# 02_MCU.net
KiCad netlist of a schematic drawn in Altium Designer
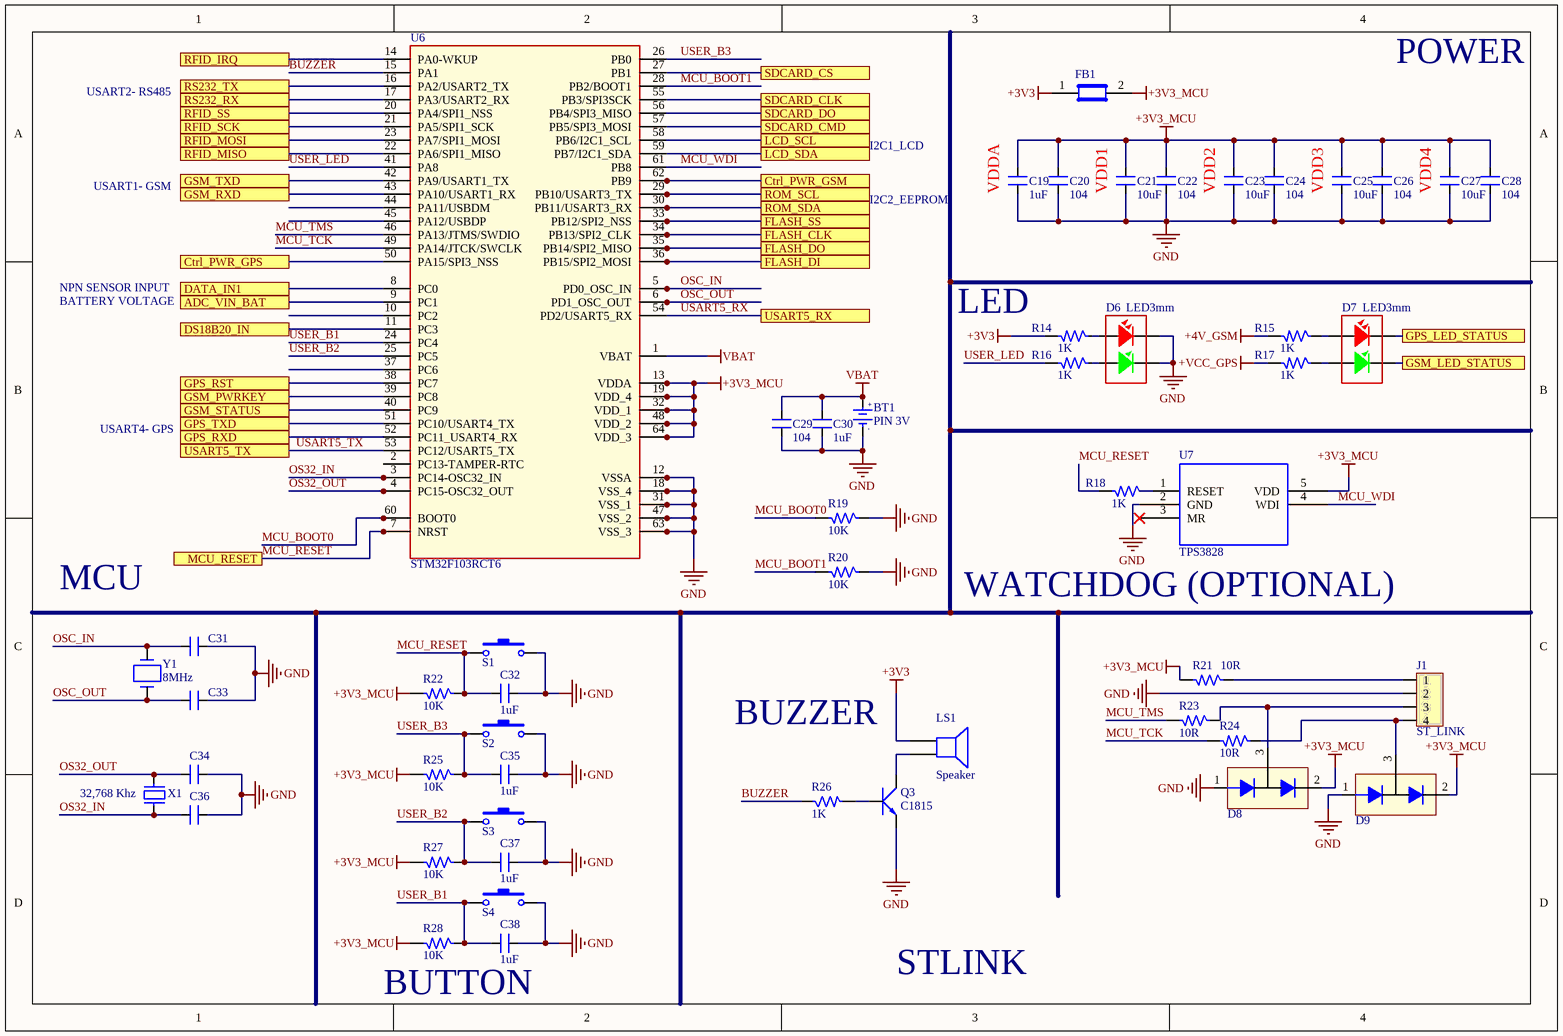
[diagram p0: [02]MCU.SchDoc]

(export (version "E")
  (design (tool "Eeschema 10.0.6"))
  (components
    (comp (ref "BT1")
      (value "PIN 3V")
      (footprint "My Library:CR1220 SMD")
      (description "Battery 3VDC")
      (libsource (lib "My Library") (part "PIN 3V"))
    )
    (comp (ref "C19")
      (value "1uF")
      (footprint "C0603 SMT")
      (description "Cap SMD")
      (libsource (lib "GPS_Traking_V1_1") (part "CM"))
    )
    (comp (ref "C20")
      (value "104")
      (footprint "C0603 SMT")
      (description "Cap SMD")
      (libsource (lib "GPS_Traking_V1_1") (part "CM"))
    )
    (comp (ref "C21")
      (value "10uF")
      (footprint "C0603 SMT")
      (description "Cap SMD")
      (libsource (lib "GPS_Traking_V1_1") (part "CM"))
    )
    (comp (ref "C22")
      (value "104")
      (footprint "C0603 SMT")
      (description "Cap SMD")
      (libsource (lib "GPS_Traking_V1_1") (part "CM"))
    )
    (comp (ref "C23")
      (value "10uF")
      (footprint "C0603 SMT")
      (description "Cap SMD")
      (libsource (lib "GPS_Traking_V1_1") (part "CM"))
    )
    (comp (ref "C24")
      (value "104")
      (footprint "C0603 SMT")
      (description "Cap SMD")
      (libsource (lib "GPS_Traking_V1_1") (part "CM"))
    )
    (comp (ref "C25")
      (value "10uF")
      (footprint "C0603 SMT")
      (description "Cap SMD")
      (libsource (lib "GPS_Traking_V1_1") (part "CM"))
    )
    (comp (ref "C26")
      (value "104")
      (footprint "C0603 SMT")
      (description "Cap SMD")
      (libsource (lib "GPS_Traking_V1_1") (part "CM"))
    )
    (comp (ref "C27")
      (value "10uF")
      (footprint "C0603 SMT")
      (description "Cap SMD")
      (libsource (lib "GPS_Traking_V1_1") (part "CM"))
    )
    (comp (ref "C28")
      (value "104")
      (footprint "C0603 SMT")
      (description "Cap SMD")
      (libsource (lib "GPS_Traking_V1_1") (part "CM"))
    )
    (comp (ref "C29")
      (value "104")
      (footprint "C0603 SMT")
      (description "Cap SMD")
      (libsource (lib "GPS_Traking_V1_1") (part "CM"))
    )
    (comp (ref "C30")
      (value "1uF")
      (footprint "C0603 SMT")
      (description "Cap SMD")
      (libsource (lib "GPS_Traking_V1_1") (part "CM"))
    )
    (comp (ref "C31")
      (value "22pF")
      (footprint "C0603 SMT")
      (description "Cap SMD")
      (libsource (lib "GPS_Traking_V1_1") (part "CM"))
    )
    (comp (ref "C32")
      (value "1uF")
      (footprint "C0603 SMT")
      (description "Cap SMD")
      (libsource (lib "GPS_Traking_V1_1") (part "CM"))
    )
    (comp (ref "C33")
      (value "22pF")
      (footprint "C0603 SMT")
      (description "Cap SMD")
      (libsource (lib "GPS_Traking_V1_1") (part "CM"))
    )
    (comp (ref "C34")
      (value "10pF")
      (footprint "C0603 SMT")
      (description "Cap SMD")
      (libsource (lib "GPS_Traking_V1_1") (part "CM"))
    )
    (comp (ref "C35")
      (value "1uF")
      (footprint "C0603 SMT")
      (description "Cap SMD")
      (libsource (lib "GPS_Traking_V1_1") (part "CM"))
    )
    (comp (ref "C36")
      (value "10pF")
      (footprint "C0603 SMT")
      (description "Cap SMD")
      (libsource (lib "GPS_Traking_V1_1") (part "CM"))
    )
    (comp (ref "C37")
      (value "1uF")
      (footprint "C0603 SMT")
      (description "Cap SMD")
      (libsource (lib "GPS_Traking_V1_1") (part "CM"))
    )
    (comp (ref "C38")
      (value "1uF")
      (footprint "C0603 SMT")
      (description "Cap SMD")
      (libsource (lib "GPS_Traking_V1_1") (part "CM"))
    )
    (comp (ref "D6")
      (value "LED3mm")
      (footprint "GPS_Traking_V1_1:LED 2 holder 3mm")
      (description "LED 2 holder RGB 3mm")
      (libsource (lib "GPS_Traking_V1_1") (part "LED2Holder_3mm"))
    )
    (comp (ref "D7")
      (value "LED3mm")
      (footprint "GPS_Traking_V1_1:LED 2 holder 3mm")
      (description "LED 2 holder RGB 3mm")
      (libsource (lib "GPS_Traking_V1_1") (part "LED2Holder_3mm"))
    )
    (comp (ref "D8")
      (value "DIODE-BAV99")
      (footprint "SOT23")
      (description "ZENER, SOT23,")
      (fields
        (field (name "MANUFACTURER") "ON Semiconductor / Fairchild")
        (field (name "MANUFACTURER PART NUMBER") "BAV99")
        (field (name ".CREATOR") "LeKhaLinh")
        (field (name ".CHECKPCB") "LeKhaLinh")
        (field (name ".CHECKSCH") "LeKhaLinh")
      )
      (libsource (lib "GPS_Traking_V1_1") (part "DIODE-BAV99"))
    )
    (comp (ref "D9")
      (value "DIODE-BAV99")
      (footprint "SOT23")
      (description "ZENER, SOT23,")
      (fields
        (field (name "MANUFACTURER") "ON Semiconductor / Fairchild")
        (field (name "MANUFACTURER PART NUMBER") "BAV99")
        (field (name ".CREATOR") "LeKhaLinh")
        (field (name ".CHECKPCB") "LeKhaLinh")
        (field (name ".CHECKSCH") "LeKhaLinh")
      )
      (libsource (lib "GPS_Traking_V1_1") (part "DIODE-BAV99"))
    )
    (comp (ref "FB1")
      (value "BLM21PG600SN1D")
      (footprint "RES-SMD-0805")
      (description "Ferrite Bead")
      (libsource (lib "khapham") (part "Ferrite Bead"))
    )
    (comp (ref "J1")
      (value "ST_LINK")
      (footprint "CON_4P")
      (description "Header IDC, 4 x 1 Pin Vertical 2.54mm Pitch (Non-Boxed, Male)")
      (fields
        (field (name "MANUFACTURER") "Würth Elektronik eiSos GmbH")
        (field (name "PARTNO") "613002143121")
        (field (name "CREATED BY") "Karrer Zheng")
      )
      (libsource (lib "My Library") (part "Header4"))
    )
    (comp (ref "LS1")
      (value "Speaker")
      (footprint "SPEAKER")
      (description "Loudspeaker")
      (fields (field (name "PUBLISHER") "Altium Limited"))
      (libsource (lib "My Library") (part "Speaker"))
    )
    (comp (ref "Q3")
      (value "C1815")
      (footprint "SOT23B")
      (description "NPN 600mW, ECB")
      (libsource (lib "GPS_Traking_V1_1") (part "C1815"))
    )
    (comp (ref "R14")
      (value "1K")
      (footprint "RES-SMD-0805")
      (description "Resistor SMD")
      (libsource (lib "GPS_Traking_V1_1") (part "RM"))
    )
    (comp (ref "R15")
      (value "1K")
      (footprint "RES-SMD-0805")
      (description "Resistor SMD")
      (libsource (lib "GPS_Traking_V1_1") (part "RM"))
    )
    (comp (ref "R16")
      (value "1K")
      (footprint "RES-SMD-0805")
      (description "Resistor SMD")
      (libsource (lib "GPS_Traking_V1_1") (part "RM"))
    )
    (comp (ref "R17")
      (value "1K")
      (footprint "RES-SMD-0805")
      (description "Resistor SMD")
      (libsource (lib "GPS_Traking_V1_1") (part "RM"))
    )
    (comp (ref "R18")
      (value "1K")
      (footprint "RES-SMD-0603")
      (description "Resistor SMD")
      (libsource (lib "GPS_Traking_V1_1") (part "RM"))
    )
    (comp (ref "R19")
      (value "10K")
      (footprint "R0603 -SMT")
      (description "Resistor SMD")
      (libsource (lib "GPS_Traking_V1_1") (part "RM"))
    )
    (comp (ref "R20")
      (value "10K")
      (footprint "R0603 -SMT")
      (description "Resistor SMD")
      (libsource (lib "GPS_Traking_V1_1") (part "RM"))
    )
    (comp (ref "R21")
      (value "10R")
      (footprint "RES-SMD-0603")
      (description "Resistor SMD")
      (libsource (lib "GPS_Traking_V1_1") (part "RM"))
    )
    (comp (ref "R22")
      (value "10K")
      (footprint "R0603 -SMT")
      (description "Resistor SMD")
      (libsource (lib "GPS_Traking_V1_1") (part "RM"))
    )
    (comp (ref "R23")
      (value "10R")
      (footprint "RES-SMD-0603")
      (description "Resistor SMD")
      (libsource (lib "GPS_Traking_V1_1") (part "RM"))
    )
    (comp (ref "R24")
      (value "10R")
      (footprint "RES-SMD-0603")
      (description "Resistor SMD")
      (libsource (lib "GPS_Traking_V1_1") (part "RM"))
    )
    (comp (ref "R25")
      (value "10K")
      (footprint "R0603 -SMT")
      (description "Resistor SMD")
      (libsource (lib "GPS_Traking_V1_1") (part "RM"))
    )
    (comp (ref "R26")
      (value "1K")
      (footprint "R0603 -SMT")
      (description "Resistor SMD")
      (libsource (lib "GPS_Traking_V1_1") (part "RM"))
    )
    (comp (ref "R27")
      (value "10K")
      (footprint "R0603 -SMT")
      (description "Resistor SMD")
      (libsource (lib "GPS_Traking_V1_1") (part "RM"))
    )
    (comp (ref "R28")
      (value "10K")
      (footprint "R0603 -SMT")
      (description "Resistor SMD")
      (libsource (lib "GPS_Traking_V1_1") (part "RM"))
    )
    (comp (ref "S1")
      (value "SW-SMD")
      (footprint "SW-SMD")
      (description "Switch")
      (fields (field (name "PUBLISHER") "Altium Limited"))
      (libsource (lib "My Library") (part "SW-SMD"))
    )
    (comp (ref "S2")
      (value "SW-SMD")
      (footprint "BUTTON NGHIENG")
      (description "Switch")
      (fields (field (name "PUBLISHER") "Altium Limited"))
      (libsource (lib "My Library") (part "SW-SMD"))
    )
    (comp (ref "S3")
      (value "SW-SMD")
      (footprint "BUTTON NGHIENG")
      (description "Switch")
      (fields (field (name "PUBLISHER") "Altium Limited"))
      (libsource (lib "My Library") (part "SW-SMD"))
    )
    (comp (ref "S4")
      (value "SW-SMD")
      (footprint "BUTTON NGHIENG")
      (description "Switch")
      (fields (field (name "PUBLISHER") "Altium Limited"))
      (libsource (lib "My Library") (part "SW-SMD"))
    )
    (comp (ref "U6")
      (value "STM32F103RCT6")
      (footprint "LQFP-64")
      (description "MCU 32BIT 256KB FLASH 64LQFP")
      (libsource (lib "GPS_Traking_V1_1") (part "STM32F103RCT6"))
    )
    (comp (ref "U7")
      (value "TPS3828")
      (footprint "TPS3828")
      (libsource (lib "GPS_Traking_V1_1") (part "TPS3828"))
    )
    (comp (ref "X1")
      (value "32,768 Khz")
      (footprint "XT32kn")
      (description "Crystal 32,768kHz for timer real")
      (libsource (lib "GPS_Traking_V1_1") (part "XT32k"))
    )
    (comp (ref "Y1")
      (value "8MHz")
      (footprint "GPS_Traking_V1_1:ABM7_v1_1_BIG")
      (description "CRYSTAL 16MHZ 18PF SMD")
      (fields
        (field (name "MANUFACTURER") "Abracon LLC")
        (field (name "MANUFACTURER PART NUMBER") "ABM7-16.000MHZ-D2Y-T")
        (field (name ".CREATOR") "MM")
        (field (name ".CHECKED PCB") "RF")
        (field (name ".CHECKED SCH") "RF")
      )
      (libsource (lib "GPS_Traking_V1_1") (part "ABM7-16.000MHZ-D2Y-T"))
    )
  )
  (nets
    (net (code "1") (name "+3V3") (class "Default")
      (node (ref "FB1") (pin "1") (pinfunction "1_1") (pintype "passive"))
      (node (ref "LS1") (pin "1") (pinfunction "1_1") (pintype "passive"))
      (node (ref "R14") (pin "2") (pinfunction "2_2") (pintype "passive"))
    )
    (net (code "2") (name "+3V3_MCU") (class "Default")
      (node (ref "C19") (pin "2") (pinfunction "2_2") (pintype "passive"))
      (node (ref "C20") (pin "2") (pinfunction "2_2") (pintype "passive"))
      (node (ref "C21") (pin "2") (pinfunction "2_2") (pintype "passive"))
      (node (ref "C22") (pin "2") (pinfunction "2_2") (pintype "passive"))
      (node (ref "C23") (pin "2") (pinfunction "2_2") (pintype "passive"))
      (node (ref "C24") (pin "2") (pinfunction "2_2") (pintype "passive"))
      (node (ref "C25") (pin "2") (pinfunction "2_2") (pintype "passive"))
      (node (ref "C26") (pin "2") (pinfunction "2_2") (pintype "passive"))
      (node (ref "C27") (pin "2") (pinfunction "2_2") (pintype "passive"))
      (node (ref "C28") (pin "2") (pinfunction "2_2") (pintype "passive"))
      (node (ref "D8") (pin "2") (pinfunction "2_2") (pintype "passive"))
      (node (ref "D9") (pin "2") (pinfunction "2_2") (pintype "passive"))
      (node (ref "FB1") (pin "2") (pinfunction "2_2") (pintype "passive"))
      (node (ref "R21") (pin "2") (pinfunction "2_2") (pintype "passive"))
      (node (ref "R22") (pin "2") (pinfunction "2_2") (pintype "passive"))
      (node (ref "R25") (pin "2") (pinfunction "2_2") (pintype "passive"))
      (node (ref "R27") (pin "2") (pinfunction "2_2") (pintype "passive"))
      (node (ref "R28") (pin "2") (pinfunction "2_2") (pintype "passive"))
      (node (ref "U6") (pin "13") (pinfunction "VDDA_13") (pintype "passive"))
      (node (ref "U6") (pin "19") (pinfunction "VDD_4_19") (pintype "passive"))
      (node (ref "U6") (pin "32") (pinfunction "VDD_1_32") (pintype "passive"))
      (node (ref "U6") (pin "48") (pinfunction "VDD_2_48") (pintype "passive"))
      (node (ref "U6") (pin "64") (pinfunction "VDD_3_64") (pintype "passive"))
      (node (ref "U7") (pin "5") (pinfunction "VDD_5") (pintype "power_in"))
    )
    (net (code "3") (name "+4V_GSM") (class "Default")
      (node (ref "R15") (pin "2") (pinfunction "2_2") (pintype "passive"))
    )
    (net (code "4") (name "+VCC_GPS") (class "Default")
      (node (ref "R17") (pin "2") (pinfunction "2_2") (pintype "passive"))
    )
    (net (code "5") (name "/ADC_VIN_BAT") (class "Default")
      (node (ref "U6") (pin "9") (pinfunction "PC1_9") (pintype "passive"))
    )
    (net (code "6") (name "/BUZZER") (class "Default")
      (node (ref "R26") (pin "1") (pinfunction "1_1") (pintype "passive"))
      (node (ref "U6") (pin "15") (pinfunction "PA1_15") (pintype "passive"))
    )
    (net (code "7") (name "/Ctrl_PWR_GPS") (class "Default")
      (node (ref "U6") (pin "50") (pinfunction "PA15/SPI3_NSS_50") (pintype "passive"))
    )
    (net (code "8") (name "/Ctrl_PWR_GSM") (class "Default")
      (node (ref "U6") (pin "62") (pinfunction "PB9_62") (pintype "passive"))
    )
    (net (code "9") (name "/DATA_IN1") (class "Default")
      (node (ref "U6") (pin "8") (pinfunction "PC0_8") (pintype "passive"))
    )
    (net (code "10") (name "/DS18B20_IN") (class "Default")
      (node (ref "U6") (pin "11") (pinfunction "PC3_11") (pintype "passive"))
    )
    (net (code "11") (name "/FLASH_CLK") (class "Default")
      (node (ref "U6") (pin "34") (pinfunction "PB13/SPI2_CLK_34") (pintype "passive"))
    )
    (net (code "12") (name "/FLASH_DI") (class "Default")
      (node (ref "U6") (pin "36") (pinfunction "PB15/SPI2_MOSI_36") (pintype "passive"))
    )
    (net (code "13") (name "/FLASH_DO") (class "Default")
      (node (ref "U6") (pin "35") (pinfunction "PB14/SPI2_MISO_35") (pintype "passive"))
    )
    (net (code "14") (name "/FLASH_SS") (class "Default")
      (node (ref "U6") (pin "33") (pinfunction "PB12/SPI2_NSS_33") (pintype "passive"))
    )
    (net (code "15") (name "/GPS_LED_STATUS") (class "Default")
      (node (ref "D7") (pin "1") (pinfunction "1_1") (pintype "passive"))
    )
    (net (code "16") (name "/GPS_RST") (class "Default")
      (node (ref "U6") (pin "38") (pinfunction "PC7_38") (pintype "passive"))
    )
    (net (code "17") (name "/GPS_RXD") (class "Default")
      (node (ref "U6") (pin "52") (pinfunction "PC11_USART4_RX_52") (pintype "passive"))
    )
    (net (code "18") (name "/GPS_TXD") (class "Default")
      (node (ref "U6") (pin "51") (pinfunction "PC10/USART4_TX_51") (pintype "passive"))
    )
    (net (code "19") (name "/GSM_LED_STATUS") (class "Default")
      (node (ref "D7") (pin "3") (pinfunction "3_3") (pintype "passive"))
    )
    (net (code "20") (name "/GSM_PWRKEY") (class "Default")
      (node (ref "U6") (pin "39") (pinfunction "PC8_39") (pintype "passive"))
    )
    (net (code "21") (name "/GSM_RXD") (class "Default")
      (node (ref "U6") (pin "43") (pinfunction "PA10/USART1_RX_43") (pintype "passive"))
    )
    (net (code "22") (name "/GSM_STATUS") (class "Default")
      (node (ref "U6") (pin "40") (pinfunction "PC9_40") (pintype "passive"))
    )
    (net (code "23") (name "/GSM_TXD") (class "Default")
      (node (ref "U6") (pin "42") (pinfunction "PA9/USART1_TX_42") (pintype "passive"))
    )
    (net (code "24") (name "/LCD_SCL") (class "Default")
      (node (ref "U6") (pin "58") (pinfunction "PB6/I2C1_SCL_58") (pintype "passive"))
    )
    (net (code "25") (name "/LCD_SDA") (class "Default")
      (node (ref "U6") (pin "59") (pinfunction "PB7/I2C1_SDA_59") (pintype "passive"))
    )
    (net (code "26") (name "/MCU_BOOT0") (class "Default")
      (node (ref "R19") (pin "2") (pinfunction "2_2") (pintype "passive"))
      (node (ref "U6") (pin "60") (pinfunction "BOOT0_60") (pintype "passive"))
    )
    (net (code "27") (name "/MCU_BOOT1") (class "Default")
      (node (ref "R20") (pin "2") (pinfunction "2_2") (pintype "passive"))
      (node (ref "U6") (pin "28") (pinfunction "PB2/BOOT1_28") (pintype "passive"))
    )
    (net (code "28") (name "/MCU_RESET") (class "Default")
      (node (ref "C32") (pin "1") (pinfunction "1_1") (pintype "passive"))
      (node (ref "R18") (pin "2") (pinfunction "2_2") (pintype "passive"))
      (node (ref "R22") (pin "1") (pinfunction "1_1") (pintype "passive"))
      (node (ref "S1") (pin "1") (pinfunction "1_1") (pintype "passive"))
      (node (ref "U6") (pin "7") (pinfunction "NRST_7") (pintype "passive"))
    )
    (net (code "29") (name "/MCU_TCK") (class "Default")
      (node (ref "R24") (pin "2") (pinfunction "2_2") (pintype "passive"))
      (node (ref "U6") (pin "49") (pinfunction "PA14/JTCK/SWCLK_49") (pintype "passive"))
    )
    (net (code "30") (name "/MCU_TMS") (class "Default")
      (node (ref "R23") (pin "2") (pinfunction "2_2") (pintype "passive"))
      (node (ref "U6") (pin "46") (pinfunction "PA13/JTMS/SWDIO_46") (pintype "passive"))
    )
    (net (code "31") (name "/MCU_WDI") (class "Default")
      (node (ref "U6") (pin "61") (pinfunction "PB8_61") (pintype "passive"))
      (node (ref "U7") (pin "4") (pinfunction "WDI_4") (pintype "passive"))
    )
    (net (code "32") (name "/OS32_IN") (class "Default")
      (node (ref "C36") (pin "1") (pinfunction "1_1") (pintype "passive"))
      (node (ref "U6") (pin "3") (pinfunction "PC14-OSC32_IN_3") (pintype "passive"))
      (node (ref "X1") (pin "1") (pinfunction "1_1") (pintype "passive"))
    )
    (net (code "33") (name "/OS32_OUT") (class "Default")
      (node (ref "C34") (pin "1") (pinfunction "1_1") (pintype "passive"))
      (node (ref "U6") (pin "4") (pinfunction "PC15-OSC32_OUT_4") (pintype "passive"))
      (node (ref "X1") (pin "2") (pinfunction "2_2") (pintype "passive"))
    )
    (net (code "34") (name "/OSC_IN") (class "Default")
      (node (ref "C31") (pin "1") (pinfunction "1_1") (pintype "passive"))
      (node (ref "U6") (pin "5") (pinfunction "PD0_OSC_IN_5") (pintype "passive"))
      (node (ref "Y1") (pin "2") (pinfunction "2_2") (pintype "passive"))
    )
    (net (code "35") (name "/OSC_OUT") (class "Default")
      (node (ref "C33") (pin "1") (pinfunction "1_1") (pintype "passive"))
      (node (ref "U6") (pin "6") (pinfunction "PD1_OSC_OUT_6") (pintype "passive"))
      (node (ref "Y1") (pin "1") (pinfunction "1_1") (pintype "passive"))
    )
    (net (code "36") (name "/RFID_IRQ") (class "Default")
      (node (ref "U6") (pin "14") (pinfunction "PA0-WKUP_14") (pintype "passive"))
    )
    (net (code "37") (name "/RFID_MISO") (class "Default")
      (node (ref "U6") (pin "22") (pinfunction "PA6/SPI1_MISO_22") (pintype "passive"))
    )
    (net (code "38") (name "/RFID_MOSI") (class "Default")
      (node (ref "U6") (pin "23") (pinfunction "PA7/SPI1_MOSI_23") (pintype "passive"))
    )
    (net (code "39") (name "/RFID_SCK") (class "Default")
      (node (ref "U6") (pin "21") (pinfunction "PA5/SPI1_SCK_21") (pintype "passive"))
    )
    (net (code "40") (name "/RFID_SS") (class "Default")
      (node (ref "U6") (pin "20") (pinfunction "PA4/SPI1_NSS_20") (pintype "passive"))
    )
    (net (code "41") (name "/ROM_SCL") (class "Default")
      (node (ref "U6") (pin "29") (pinfunction "PB10/USART3_TX_29") (pintype "passive"))
    )
    (net (code "42") (name "/ROM_SDA") (class "Default")
      (node (ref "U6") (pin "30") (pinfunction "PB11/USART3_RX_30") (pintype "passive"))
    )
    (net (code "43") (name "/RS232_RX") (class "Default")
      (node (ref "U6") (pin "17") (pinfunction "PA3/USART2_RX_17") (pintype "passive"))
    )
    (net (code "44") (name "/RS232_TX") (class "Default")
      (node (ref "U6") (pin "16") (pinfunction "PA2/USART2_TX_16") (pintype "passive"))
    )
    (net (code "45") (name "/SDCARD_CLK") (class "Default")
      (node (ref "U6") (pin "55") (pinfunction "PB3/SPI3SCK_55") (pintype "passive"))
    )
    (net (code "46") (name "/SDCARD_CMD") (class "Default")
      (node (ref "U6") (pin "57") (pinfunction "PB5/SPI3_MOSI_57") (pintype "passive"))
    )
    (net (code "47") (name "/SDCARD_CS") (class "Default")
      (node (ref "U6") (pin "27") (pinfunction "PB1_27") (pintype "passive"))
    )
    (net (code "48") (name "/SDCARD_DO") (class "Default")
      (node (ref "U6") (pin "56") (pinfunction "PB4/SPI3_MISO_56") (pintype "passive"))
    )
    (net (code "49") (name "/USART5_RX") (class "Default")
      (node (ref "U6") (pin "54") (pinfunction "PD2/USART5_RX_54") (pintype "passive"))
    )
    (net (code "50") (name "/USART5_TX") (class "Default")
      (node (ref "U6") (pin "53") (pinfunction "PC12/USART5_TX_53") (pintype "passive"))
    )
    (net (code "51") (name "/USER_B1") (class "Default")
      (node (ref "C38") (pin "1") (pinfunction "1_1") (pintype "passive"))
      (node (ref "R28") (pin "1") (pinfunction "1_1") (pintype "passive"))
      (node (ref "S4") (pin "1") (pinfunction "1_1") (pintype "passive"))
      (node (ref "U6") (pin "24") (pinfunction "PC4_24") (pintype "passive"))
    )
    (net (code "52") (name "/USER_B2") (class "Default")
      (node (ref "C37") (pin "1") (pinfunction "1_1") (pintype "passive"))
      (node (ref "R27") (pin "1") (pinfunction "1_1") (pintype "passive"))
      (node (ref "S3") (pin "1") (pinfunction "1_1") (pintype "passive"))
      (node (ref "U6") (pin "25") (pinfunction "PC5_25") (pintype "passive"))
    )
    (net (code "53") (name "/USER_B3") (class "Default")
      (node (ref "C35") (pin "1") (pinfunction "1_1") (pintype "passive"))
      (node (ref "R25") (pin "1") (pinfunction "1_1") (pintype "passive"))
      (node (ref "S2") (pin "1") (pinfunction "1_1") (pintype "passive"))
      (node (ref "U6") (pin "26") (pinfunction "PB0_26") (pintype "passive"))
    )
    (net (code "54") (name "/USER_LED") (class "Default")
      (node (ref "R16") (pin "2") (pinfunction "2_2") (pintype "passive"))
      (node (ref "U6") (pin "41") (pinfunction "PA8_41") (pintype "passive"))
    )
    (net (code "55") (name "GND") (class "Default")
      (node (ref "BT1") (pin "2") (pinfunction "GND_2") (pintype "passive"))
      (node (ref "C19") (pin "1") (pinfunction "1_1") (pintype "passive"))
      (node (ref "C20") (pin "1") (pinfunction "1_1") (pintype "passive"))
      (node (ref "C21") (pin "1") (pinfunction "1_1") (pintype "passive"))
      (node (ref "C22") (pin "1") (pinfunction "1_1") (pintype "passive"))
      (node (ref "C23") (pin "1") (pinfunction "1_1") (pintype "passive"))
      (node (ref "C24") (pin "1") (pinfunction "1_1") (pintype "passive"))
      (node (ref "C25") (pin "1") (pinfunction "1_1") (pintype "passive"))
      (node (ref "C26") (pin "1") (pinfunction "1_1") (pintype "passive"))
      (node (ref "C27") (pin "1") (pinfunction "1_1") (pintype "passive"))
      (node (ref "C28") (pin "1") (pinfunction "1_1") (pintype "passive"))
      (node (ref "C29") (pin "1") (pinfunction "1_1") (pintype "passive"))
      (node (ref "C30") (pin "1") (pinfunction "1_1") (pintype "passive"))
      (node (ref "C31") (pin "2") (pinfunction "2_2") (pintype "passive"))
      (node (ref "C32") (pin "2") (pinfunction "2_2") (pintype "passive"))
      (node (ref "C33") (pin "2") (pinfunction "2_2") (pintype "passive"))
      (node (ref "C34") (pin "2") (pinfunction "2_2") (pintype "passive"))
      (node (ref "C35") (pin "2") (pinfunction "2_2") (pintype "passive"))
      (node (ref "C36") (pin "2") (pinfunction "2_2") (pintype "passive"))
      (node (ref "C37") (pin "2") (pinfunction "2_2") (pintype "passive"))
      (node (ref "C38") (pin "2") (pinfunction "2_2") (pintype "passive"))
      (node (ref "D6") (pin "1") (pinfunction "1_1") (pintype "passive"))
      (node (ref "D6") (pin "3") (pinfunction "3_3") (pintype "passive"))
      (node (ref "D8") (pin "1") (pinfunction "1_1") (pintype "passive"))
      (node (ref "D9") (pin "1") (pinfunction "1_1") (pintype "passive"))
      (node (ref "J1") (pin "2") (pinfunction "2_2") (pintype "passive"))
      (node (ref "Q3") (pin "1") (pinfunction "E_1") (pintype "passive"))
      (node (ref "R19") (pin "1") (pinfunction "1_1") (pintype "passive"))
      (node (ref "R20") (pin "1") (pinfunction "1_1") (pintype "passive"))
      (node (ref "S1") (pin "2") (pinfunction "2_2") (pintype "passive"))
      (node (ref "S2") (pin "2") (pinfunction "2_2") (pintype "passive"))
      (node (ref "S3") (pin "2") (pinfunction "2_2") (pintype "passive"))
      (node (ref "S4") (pin "2") (pinfunction "2_2") (pintype "passive"))
      (node (ref "U6") (pin "12") (pinfunction "VSSA_12") (pintype "passive"))
      (node (ref "U6") (pin "18") (pinfunction "VSS_4_18") (pintype "passive"))
      (node (ref "U6") (pin "31") (pinfunction "VSS_1_31") (pintype "passive"))
      (node (ref "U6") (pin "47") (pinfunction "VSS_2_47") (pintype "passive"))
      (node (ref "U6") (pin "63") (pinfunction "VSS_3_63") (pintype "passive"))
      (node (ref "U7") (pin "2") (pinfunction "GND_2") (pintype "power_in"))
    )
    (net (code "56") (name "Net-(D6-Pad2)") (class "Default")
      (node (ref "D6") (pin "2") (pinfunction "2_2") (pintype "passive"))
      (node (ref "R14") (pin "1") (pinfunction "1_1") (pintype "passive"))
    )
    (net (code "57") (name "Net-(D6-Pad4)") (class "Default")
      (node (ref "D6") (pin "4") (pinfunction "4_4") (pintype "passive"))
      (node (ref "R16") (pin "1") (pinfunction "1_1") (pintype "passive"))
    )
    (net (code "58") (name "Net-(D7-Pad2)") (class "Default")
      (node (ref "D7") (pin "2") (pinfunction "2_2") (pintype "passive"))
      (node (ref "R15") (pin "1") (pinfunction "1_1") (pintype "passive"))
    )
    (net (code "59") (name "Net-(D7-Pad4)") (class "Default")
      (node (ref "D7") (pin "4") (pinfunction "4_4") (pintype "passive"))
      (node (ref "R17") (pin "1") (pinfunction "1_1") (pintype "passive"))
    )
    (net (code "60") (name "Net-(D8-Pad3)") (class "Default")
      (node (ref "D8") (pin "3") (pinfunction "3_3") (pintype "passive"))
      (node (ref "J1") (pin "3") (pinfunction "3_3") (pintype "passive"))
      (node (ref "R23") (pin "1") (pinfunction "1_1") (pintype "passive"))
    )
    (net (code "61") (name "Net-(D9-Pad3)") (class "Default")
      (node (ref "D9") (pin "3") (pinfunction "3_3") (pintype "passive"))
      (node (ref "J1") (pin "4") (pinfunction "4_4") (pintype "passive"))
      (node (ref "R24") (pin "1") (pinfunction "1_1") (pintype "passive"))
    )
    (net (code "62") (name "Net-(J1-Pad1)") (class "Default")
      (node (ref "J1") (pin "1") (pinfunction "1_1") (pintype "passive"))
      (node (ref "R21") (pin "1") (pinfunction "1_1") (pintype "passive"))
    )
    (net (code "63") (name "Net-(Q3-B)") (class "Default")
      (node (ref "Q3") (pin "3") (pinfunction "B_3") (pintype "passive"))
      (node (ref "R26") (pin "2") (pinfunction "2_2") (pintype "passive"))
    )
    (net (code "64") (name "Net-(Q3-C)") (class "Default")
      (node (ref "LS1") (pin "2") (pinfunction "2_2") (pintype "passive"))
      (node (ref "Q3") (pin "2") (pinfunction "C_2") (pintype "passive"))
    )
    (net (code "65") (name "Net-(U7-RESET)") (class "Default")
      (node (ref "R18") (pin "1") (pinfunction "1_1") (pintype "passive"))
      (node (ref "U7") (pin "1") (pinfunction "RESET_1") (pintype "passive"))
    )
    (net (code "66") (name "VBAT") (class "Default")
      (node (ref "BT1") (pin "1") (pinfunction "+3V_1") (pintype "passive"))
      (node (ref "C29") (pin "2") (pinfunction "2_2") (pintype "passive"))
      (node (ref "C30") (pin "2") (pinfunction "2_2") (pintype "passive"))
      (node (ref "U6") (pin "1") (pinfunction "VBAT_1") (pintype "passive"))
    )
    (net (code "67") (name "unconnected-(U6-PA11{slash}USBDM-Pad44)") (class "Default")
      (node (ref "U6") (pin "44") (pinfunction "PA11/USBDM_44") (pintype "passive"))
    )
    (net (code "68") (name "unconnected-(U6-PA12{slash}USBDP-Pad45)") (class "Default")
      (node (ref "U6") (pin "45") (pinfunction "PA12/USBDP_45") (pintype "passive"))
    )
    (net (code "69") (name "unconnected-(U6-PC2-Pad10)") (class "Default")
      (node (ref "U6") (pin "10") (pinfunction "PC2_10") (pintype "passive"))
    )
    (net (code "70") (name "unconnected-(U6-PC6-Pad37)") (class "Default")
      (node (ref "U6") (pin "37") (pinfunction "PC6_37") (pintype "passive"))
    )
    (net (code "71") (name "unconnected-(U6-PC13-TAMPER-RTC-Pad2)") (class "Default")
      (node (ref "U6") (pin "2") (pinfunction "PC13-TAMPER-RTC_2") (pintype "passive"))
    )
    (net (code "72") (name "unconnected-(U7-MR-Pad3)") (class "Default")
      (node (ref "U7") (pin "3") (pinfunction "MR_3") (pintype "passive+no_connect"))
    )
  )
)
